# Schematic_Test_Bench_Back_Scatter.net
KiCad netlist of a schematic drawn in Altium Designer
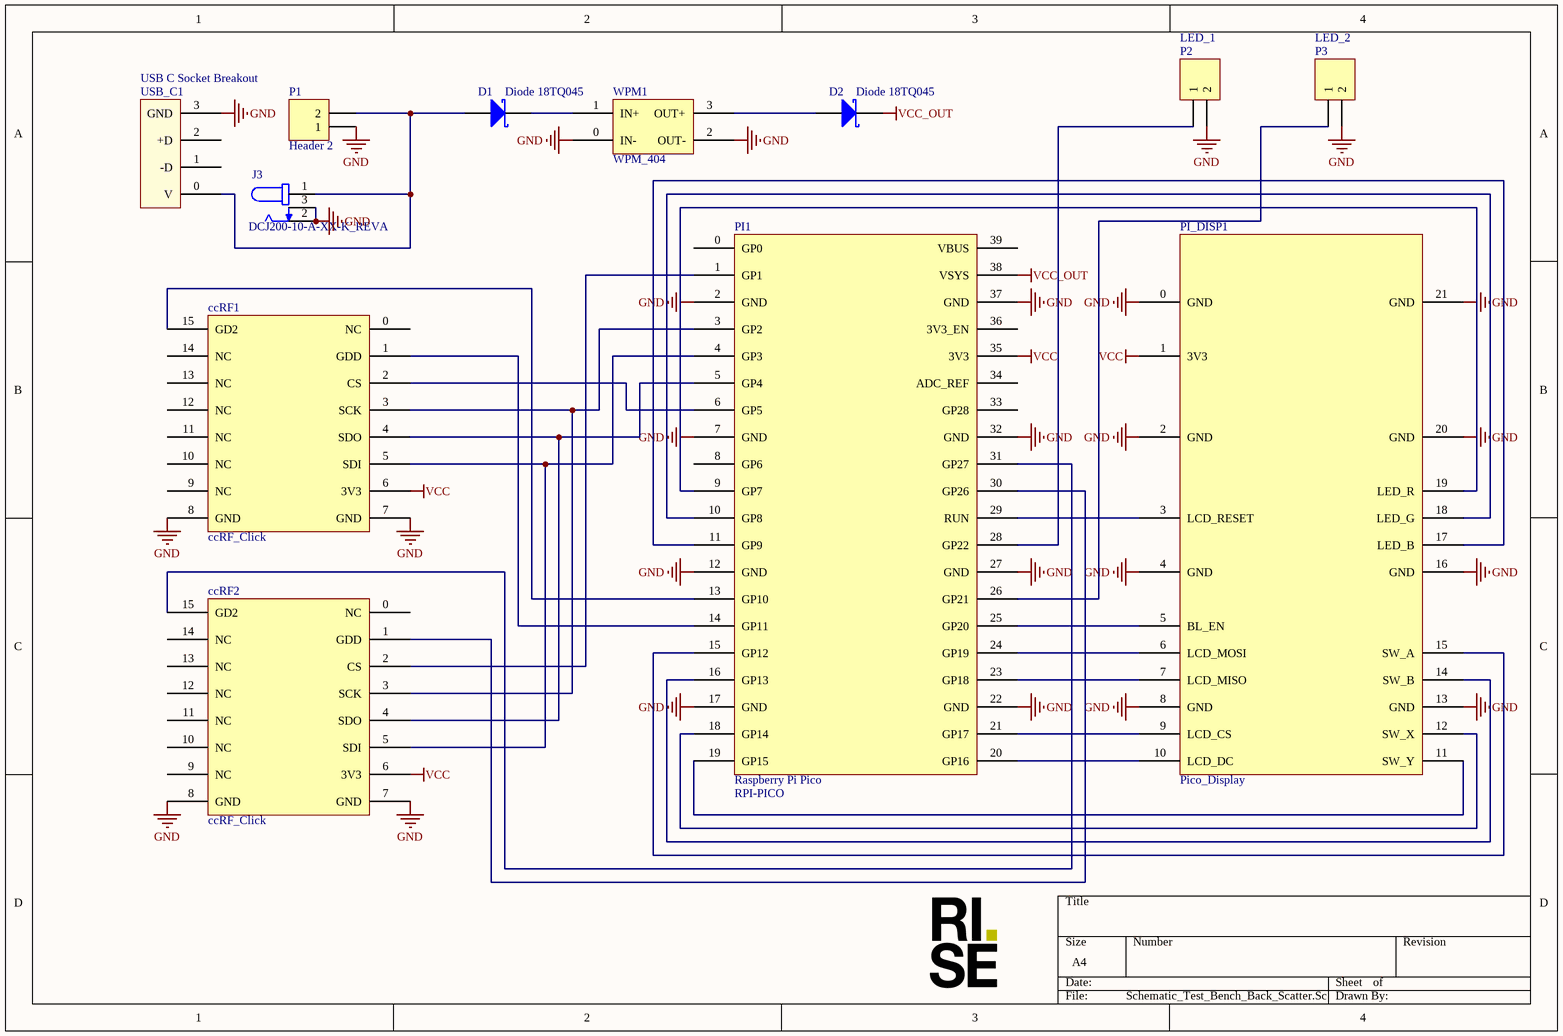
[diagram p0: Schematic_Test_Bench_Back_Scatter.SchDoc]

(export (version "E")
  (design (tool "Eeschema 10.0.6"))
  (components
    (comp (ref "*")
      (value "RISE_LOGO")
      (footprint "RISE_Logo")
      (description "RISE_Logo")
      (libsource (lib "Test_Bench_Lib") (part "RISE_LOGO"))
    )
    (comp (ref "ccRF1")
      (value "ccRF_Click")
      (footprint "CCRF_CLICK_SMD")
      (description "ccRF_Click 2480MHz radio")
      (libsource (lib "Test_Bench_Lib") (part "ccRF_Click"))
    )
    (comp (ref "ccRF2")
      (value "ccRF_Click")
      (footprint "CCRF_CLICK_SMD")
      (description "ccRF_Click 2480MHz radio")
      (libsource (lib "Test_Bench_Lib") (part "ccRF_Click"))
    )
    (comp (ref "D1")
      (value "Diode 18TQ045")
      (footprint "18TQ045-M3")
      (description "Schottky Rectifier")
      (fields (field (name "PUBLISHER") "Altium Limited"))
      (libsource (lib "Miscellaneous Devices") (part "Diode 18TQ045"))
    )
    (comp (ref "D2")
      (value "Diode 18TQ045")
      (footprint "18TQ045-M3")
      (description "Schottky Rectifier")
      (fields (field (name "PUBLISHER") "Altium Limited"))
      (libsource (lib "Miscellaneous Devices") (part "Diode 18TQ045"))
    )
    (comp (ref "J3")
      (value "DCJ200-10-A-XX-K_REVA")
      (footprint "GCT_DCJ200-10-A-XX-K_REVA")
      (description "Power Barrel Connector Jack 2.05mm ID (0.081), 5.50mm OD (0.217) Through Hole, Right Angle")
      (fields (field (name "MF") "Global Connector Technology") (field (name "MP") "DCJ200-10-A-K1-K"))
      (libsource (lib "DCJ200-10-A-XX-K_REVA") (part "DCJ200-10-A-XX-K_REVA"))
    )
    (comp (ref "P1")
      (value "Header 2")
      (footprint "HDR1X2")
      (description "Header, 2-Pin")
      (fields (field (name "PUBLISHER") "Altium Limited"))
      (libsource (lib "") (part "Header 2_1"))
    )
    (comp (ref "P2")
      (value "LED_1")
      (footprint "HDR1X2")
      (description "Header, 2-Pin")
      (fields (field (name "PUBLISHER") "Altium Limited"))
      (libsource (lib "Miscellaneous Connectors") (part "Header 2"))
    )
    (comp (ref "P3")
      (value "LED_2")
      (footprint "HDR1X2")
      (description "Header, 2-Pin")
      (fields (field (name "PUBLISHER") "Altium Limited"))
      (libsource (lib "Miscellaneous Connectors") (part "Header 2"))
    )
    (comp (ref "PI1")
      (value "Raspberry Pi Pico")
      (footprint "Raspberry Pi Pico")
      (fields (field (name "SUPPLIER PART NUMBER 1") "RPI-PICO"))
      (libsource (lib "Test_Bench_Lib") (part "Raspberry_Pi_Pico_Header"))
    )
    (comp (ref "PI_DISP1")
      (value "Pico_Display")
      (footprint "Pico_Display_Header")
      (libsource (lib "Test_Bench_Lib") (part "Pico_Display_Header"))
    )
    (comp (ref "USB_C1")
      (value "USB C Socket Breakout")
      (footprint "Simple_USB_C_Socket_Breakout")
      (description "Simple USB C Socket Breakout")
      (libsource (lib "Test_Bench_Lib") (part "USB C Socket Breakout"))
    )
    (comp (ref "WPM1")
      (value "WPM_404")
      (footprint "WPM404_SMD")
      (description "Velleman WPM404 Whadda DC-DC Adjustable Voltage Step-Down Module LM2596S")
      (libsource (lib "Test_Bench_Lib") (part "WPM_404"))
    )
  )
  (nets
    (net (code "1") (name "GND") (class "Default")
      (node (ref "J3") (pin "2") (pinfunction "2_2") (pintype "passive"))
      (node (ref "J3") (pin "3") (pinfunction "3_3") (pintype "passive"))
      (node (ref "P1") (pin "1") (pinfunction "1_1") (pintype "passive"))
      (node (ref "P2") (pin "2") (pinfunction "2_2") (pintype "passive"))
      (node (ref "P3") (pin "2") (pinfunction "2_2") (pintype "passive"))
      (node (ref "PI1") (pin "12") (pinfunction "GND_12") (pintype "passive"))
      (node (ref "PI1") (pin "17") (pinfunction "GND_17") (pintype "passive"))
      (node (ref "PI1") (pin "2") (pinfunction "GND_2") (pintype "passive"))
      (node (ref "PI1") (pin "22") (pinfunction "GND_22") (pintype "passive"))
      (node (ref "PI1") (pin "27") (pinfunction "GND_27") (pintype "passive"))
      (node (ref "PI1") (pin "32") (pinfunction "GND_32") (pintype "passive"))
      (node (ref "PI1") (pin "37") (pinfunction "GND_37") (pintype "passive"))
      (node (ref "PI1") (pin "7") (pinfunction "GND_7") (pintype "passive"))
      (node (ref "PI_DISP1") (pin "0") (pinfunction "GND_0") (pintype "passive"))
      (node (ref "PI_DISP1") (pin "13") (pinfunction "GND_13") (pintype "passive"))
      (node (ref "PI_DISP1") (pin "16") (pinfunction "GND_16") (pintype "passive"))
      (node (ref "PI_DISP1") (pin "2") (pinfunction "GND_2") (pintype "passive"))
      (node (ref "PI_DISP1") (pin "20") (pinfunction "GND_20") (pintype "passive"))
      (node (ref "PI_DISP1") (pin "21") (pinfunction "GND_21") (pintype "passive"))
      (node (ref "PI_DISP1") (pin "4") (pinfunction "GND_4") (pintype "passive"))
      (node (ref "PI_DISP1") (pin "8") (pinfunction "GND_8") (pintype "passive"))
      (node (ref "USB_C1") (pin "3") (pinfunction "GND_3") (pintype "passive"))
      (node (ref "WPM1") (pin "0") (pinfunction "IN-_0") (pintype "passive"))
      (node (ref "WPM1") (pin "2") (pinfunction "OUT-_2") (pintype "passive"))
      (node (ref "ccRF1") (pin "7") (pinfunction "GND_7") (pintype "passive"))
      (node (ref "ccRF1") (pin "8") (pinfunction "GND_8") (pintype "passive"))
      (node (ref "ccRF2") (pin "7") (pinfunction "GND_7") (pintype "passive"))
      (node (ref "ccRF2") (pin "8") (pinfunction "GND_8") (pintype "passive"))
    )
    (net (code "2") (name "Net-(D1-A)") (class "Default")
      (node (ref "D1") (pin "3") (pinfunction "A_3") (pintype "passive"))
      (node (ref "J3") (pin "1") (pinfunction "1_1") (pintype "passive"))
      (node (ref "P1") (pin "2") (pinfunction "2_2") (pintype "passive"))
      (node (ref "USB_C1") (pin "0") (pinfunction "V_0") (pintype "passive"))
    )
    (net (code "3") (name "Net-(D1-K)") (class "Default")
      (node (ref "D1") (pin "1") (pinfunction "K_1") (pintype "passive"))
      (node (ref "WPM1") (pin "1") (pinfunction "IN+_1") (pintype "passive"))
    )
    (net (code "4") (name "Net-(D2-A)") (class "Default")
      (node (ref "D2") (pin "3") (pinfunction "A_3") (pintype "passive"))
      (node (ref "WPM1") (pin "3") (pinfunction "OUT+_3") (pintype "passive"))
    )
    (net (code "5") (name "Net-(PI1-GP1)") (class "Default")
      (node (ref "PI1") (pin "1") (pinfunction "GP1_1") (pintype "passive"))
      (node (ref "ccRF2") (pin "2") (pinfunction "CS_2") (pintype "passive"))
    )
    (net (code "6") (name "Net-(PI1-GP2)") (class "Default")
      (node (ref "PI1") (pin "3") (pinfunction "GP2_3") (pintype "passive"))
      (node (ref "ccRF1") (pin "3") (pinfunction "SCK_3") (pintype "passive"))
      (node (ref "ccRF2") (pin "3") (pinfunction "SCK_3") (pintype "passive"))
    )
    (net (code "7") (name "Net-(PI1-GP3)") (class "Default")
      (node (ref "PI1") (pin "4") (pinfunction "GP3_4") (pintype "passive"))
      (node (ref "ccRF1") (pin "5") (pinfunction "SDI_5") (pintype "passive"))
      (node (ref "ccRF2") (pin "5") (pinfunction "SDI_5") (pintype "passive"))
    )
    (net (code "8") (name "Net-(PI1-GP4)") (class "Default")
      (node (ref "PI1") (pin "5") (pinfunction "GP4_5") (pintype "passive"))
      (node (ref "ccRF1") (pin "4") (pinfunction "SDO_4") (pintype "passive"))
      (node (ref "ccRF2") (pin "4") (pinfunction "SDO_4") (pintype "passive"))
    )
    (net (code "9") (name "Net-(PI1-GP5)") (class "Default")
      (node (ref "PI1") (pin "6") (pinfunction "GP5_6") (pintype "passive"))
      (node (ref "ccRF1") (pin "2") (pinfunction "CS_2") (pintype "passive"))
    )
    (net (code "10") (name "Net-(PI1-GP7)") (class "Default")
      (node (ref "PI1") (pin "9") (pinfunction "GP7_9") (pintype "passive"))
      (node (ref "PI_DISP1") (pin "19") (pinfunction "LED_R_19") (pintype "passive"))
    )
    (net (code "11") (name "Net-(PI1-GP8)") (class "Default")
      (node (ref "PI1") (pin "10") (pinfunction "GP8_10") (pintype "passive"))
      (node (ref "PI_DISP1") (pin "18") (pinfunction "LED_G_18") (pintype "passive"))
    )
    (net (code "12") (name "Net-(PI1-GP9)") (class "Default")
      (node (ref "PI1") (pin "11") (pinfunction "GP9_11") (pintype "passive"))
      (node (ref "PI_DISP1") (pin "17") (pinfunction "LED_B_17") (pintype "passive"))
    )
    (net (code "13") (name "Net-(PI1-GP10)") (class "Default")
      (node (ref "PI1") (pin "13") (pinfunction "GP10_13") (pintype "passive"))
      (node (ref "ccRF1") (pin "15") (pinfunction "GD2_15") (pintype "passive"))
    )
    (net (code "14") (name "Net-(PI1-GP11)") (class "Default")
      (node (ref "PI1") (pin "14") (pinfunction "GP11_14") (pintype "passive"))
      (node (ref "ccRF1") (pin "1") (pinfunction "GDD_1") (pintype "passive"))
    )
    (net (code "15") (name "Net-(PI1-GP12)") (class "Default")
      (node (ref "PI1") (pin "15") (pinfunction "GP12_15") (pintype "passive"))
      (node (ref "PI_DISP1") (pin "15") (pinfunction "SW_A_15") (pintype "passive"))
    )
    (net (code "16") (name "Net-(PI1-GP13)") (class "Default")
      (node (ref "PI1") (pin "16") (pinfunction "GP13_16") (pintype "passive"))
      (node (ref "PI_DISP1") (pin "14") (pinfunction "SW_B_14") (pintype "passive"))
    )
    (net (code "17") (name "Net-(PI1-GP14)") (class "Default")
      (node (ref "PI1") (pin "18") (pinfunction "GP14_18") (pintype "passive"))
      (node (ref "PI_DISP1") (pin "12") (pinfunction "SW_X_12") (pintype "passive"))
    )
    (net (code "18") (name "Net-(PI1-GP15)") (class "Default")
      (node (ref "PI1") (pin "19") (pinfunction "GP15_19") (pintype "passive"))
      (node (ref "PI_DISP1") (pin "11") (pinfunction "SW_Y_11") (pintype "passive"))
    )
    (net (code "19") (name "Net-(PI1-GP16)") (class "Default")
      (node (ref "PI1") (pin "20") (pinfunction "GP16_20") (pintype "passive"))
      (node (ref "PI_DISP1") (pin "10") (pinfunction "LCD_DC_10") (pintype "passive"))
    )
    (net (code "20") (name "Net-(PI1-GP17)") (class "Default")
      (node (ref "PI1") (pin "21") (pinfunction "GP17_21") (pintype "passive"))
      (node (ref "PI_DISP1") (pin "9") (pinfunction "LCD_CS_9") (pintype "passive"))
    )
    (net (code "21") (name "Net-(PI1-GP18)") (class "Default")
      (node (ref "PI1") (pin "23") (pinfunction "GP18_23") (pintype "passive"))
      (node (ref "PI_DISP1") (pin "7") (pinfunction "LCD_MISO_7") (pintype "passive"))
    )
    (net (code "22") (name "Net-(PI1-GP19)") (class "Default")
      (node (ref "PI1") (pin "24") (pinfunction "GP19_24") (pintype "passive"))
      (node (ref "PI_DISP1") (pin "6") (pinfunction "LCD_MOSI_6") (pintype "passive"))
    )
    (net (code "23") (name "Net-(PI1-GP20)") (class "Default")
      (node (ref "PI1") (pin "25") (pinfunction "GP20_25") (pintype "passive"))
      (node (ref "PI_DISP1") (pin "5") (pinfunction "BL_EN_5") (pintype "passive"))
    )
    (net (code "24") (name "Net-(PI1-GP21)") (class "Default")
      (node (ref "P3") (pin "1") (pinfunction "1_1") (pintype "passive"))
      (node (ref "PI1") (pin "26") (pinfunction "GP21_26") (pintype "passive"))
    )
    (net (code "25") (name "Net-(PI1-GP22)") (class "Default")
      (node (ref "P2") (pin "1") (pinfunction "1_1") (pintype "passive"))
      (node (ref "PI1") (pin "28") (pinfunction "GP22_28") (pintype "passive"))
    )
    (net (code "26") (name "Net-(PI1-GP26)") (class "Default")
      (node (ref "PI1") (pin "30") (pinfunction "GP26_30") (pintype "passive"))
      (node (ref "ccRF2") (pin "1") (pinfunction "GDD_1") (pintype "passive"))
    )
    (net (code "27") (name "Net-(PI1-GP27)") (class "Default")
      (node (ref "PI1") (pin "31") (pinfunction "GP27_31") (pintype "passive"))
      (node (ref "ccRF2") (pin "15") (pinfunction "GD2_15") (pintype "passive"))
    )
    (net (code "28") (name "Net-(PI1-RUN)") (class "Default")
      (node (ref "PI1") (pin "29") (pinfunction "RUN_29") (pintype "passive"))
      (node (ref "PI_DISP1") (pin "3") (pinfunction "LCD_RESET_3") (pintype "passive"))
    )
    (net (code "29") (name "VCC") (class "Default")
      (node (ref "PI1") (pin "35") (pinfunction "3V3_35") (pintype "passive"))
      (node (ref "PI_DISP1") (pin "1") (pinfunction "3V3_1") (pintype "passive"))
      (node (ref "ccRF1") (pin "6") (pinfunction "3V3_6") (pintype "passive"))
      (node (ref "ccRF2") (pin "6") (pinfunction "3V3_6") (pintype "passive"))
    )
    (net (code "30") (name "VCC_OUT") (class "Default")
      (node (ref "D2") (pin "1") (pinfunction "K_1") (pintype "passive"))
      (node (ref "PI1") (pin "38") (pinfunction "VSYS_38") (pintype "passive"))
    )
    (net (code "31") (name "unconnected-(PI1-3V3_EN-Pad36)") (class "Default")
      (node (ref "PI1") (pin "36") (pinfunction "3V3_EN_36") (pintype "passive"))
    )
    (net (code "32") (name "unconnected-(PI1-ADC_REF-Pad34)") (class "Default")
      (node (ref "PI1") (pin "34") (pinfunction "ADC_REF_34") (pintype "passive"))
    )
    (net (code "33") (name "unconnected-(PI1-GP0-Pad0)") (class "Default")
      (node (ref "PI1") (pin "0") (pinfunction "GP0_0") (pintype "passive"))
    )
    (net (code "34") (name "unconnected-(PI1-GP6-Pad8)") (class "Default")
      (node (ref "PI1") (pin "8") (pinfunction "GP6_8") (pintype "passive"))
    )
    (net (code "35") (name "unconnected-(PI1-GP28-Pad33)") (class "Default")
      (node (ref "PI1") (pin "33") (pinfunction "GP28_33") (pintype "passive"))
    )
    (net (code "36") (name "unconnected-(PI1-VBUS-Pad39)") (class "Default")
      (node (ref "PI1") (pin "39") (pinfunction "VBUS_39") (pintype "passive"))
    )
    (net (code "37") (name "unconnected-(USB_C1-+D-Pad2)") (class "Default")
      (node (ref "USB_C1") (pin "2") (pinfunction "+D_2") (pintype "passive"))
    )
    (net (code "38") (name "unconnected-(USB_C1--D-Pad1)") (class "Default")
      (node (ref "USB_C1") (pin "1") (pinfunction "-D_1") (pintype "passive"))
    )
    (net (code "39") (name "unconnected-(ccRF1-NC-Pad0)") (class "Default")
      (node (ref "ccRF1") (pin "0") (pinfunction "NC_0") (pintype "passive"))
    )
    (net (code "40") (name "unconnected-(ccRF1-NC-Pad9)") (class "Default")
      (node (ref "ccRF1") (pin "9") (pinfunction "NC_9") (pintype "passive"))
    )
    (net (code "41") (name "unconnected-(ccRF1-NC-Pad10)") (class "Default")
      (node (ref "ccRF1") (pin "10") (pinfunction "NC_10") (pintype "passive"))
    )
    (net (code "42") (name "unconnected-(ccRF1-NC-Pad11)") (class "Default")
      (node (ref "ccRF1") (pin "11") (pinfunction "NC_11") (pintype "passive"))
    )
    (net (code "43") (name "unconnected-(ccRF1-NC-Pad12)") (class "Default")
      (node (ref "ccRF1") (pin "12") (pinfunction "NC_12") (pintype "passive"))
    )
    (net (code "44") (name "unconnected-(ccRF1-NC-Pad13)") (class "Default")
      (node (ref "ccRF1") (pin "13") (pinfunction "NC_13") (pintype "passive"))
    )
    (net (code "45") (name "unconnected-(ccRF1-NC-Pad14)") (class "Default")
      (node (ref "ccRF1") (pin "14") (pinfunction "NC_14") (pintype "passive"))
    )
    (net (code "46") (name "unconnected-(ccRF2-NC-Pad0)") (class "Default")
      (node (ref "ccRF2") (pin "0") (pinfunction "NC_0") (pintype "passive"))
    )
    (net (code "47") (name "unconnected-(ccRF2-NC-Pad9)") (class "Default")
      (node (ref "ccRF2") (pin "9") (pinfunction "NC_9") (pintype "passive"))
    )
    (net (code "48") (name "unconnected-(ccRF2-NC-Pad10)") (class "Default")
      (node (ref "ccRF2") (pin "10") (pinfunction "NC_10") (pintype "passive"))
    )
    (net (code "49") (name "unconnected-(ccRF2-NC-Pad11)") (class "Default")
      (node (ref "ccRF2") (pin "11") (pinfunction "NC_11") (pintype "passive"))
    )
    (net (code "50") (name "unconnected-(ccRF2-NC-Pad12)") (class "Default")
      (node (ref "ccRF2") (pin "12") (pinfunction "NC_12") (pintype "passive"))
    )
    (net (code "51") (name "unconnected-(ccRF2-NC-Pad13)") (class "Default")
      (node (ref "ccRF2") (pin "13") (pinfunction "NC_13") (pintype "passive"))
    )
    (net (code "52") (name "unconnected-(ccRF2-NC-Pad14)") (class "Default")
      (node (ref "ccRF2") (pin "14") (pinfunction "NC_14") (pintype "passive"))
    )
  )
)
